# Slave.net
KiCad netlist of a schematic drawn in EAGLE
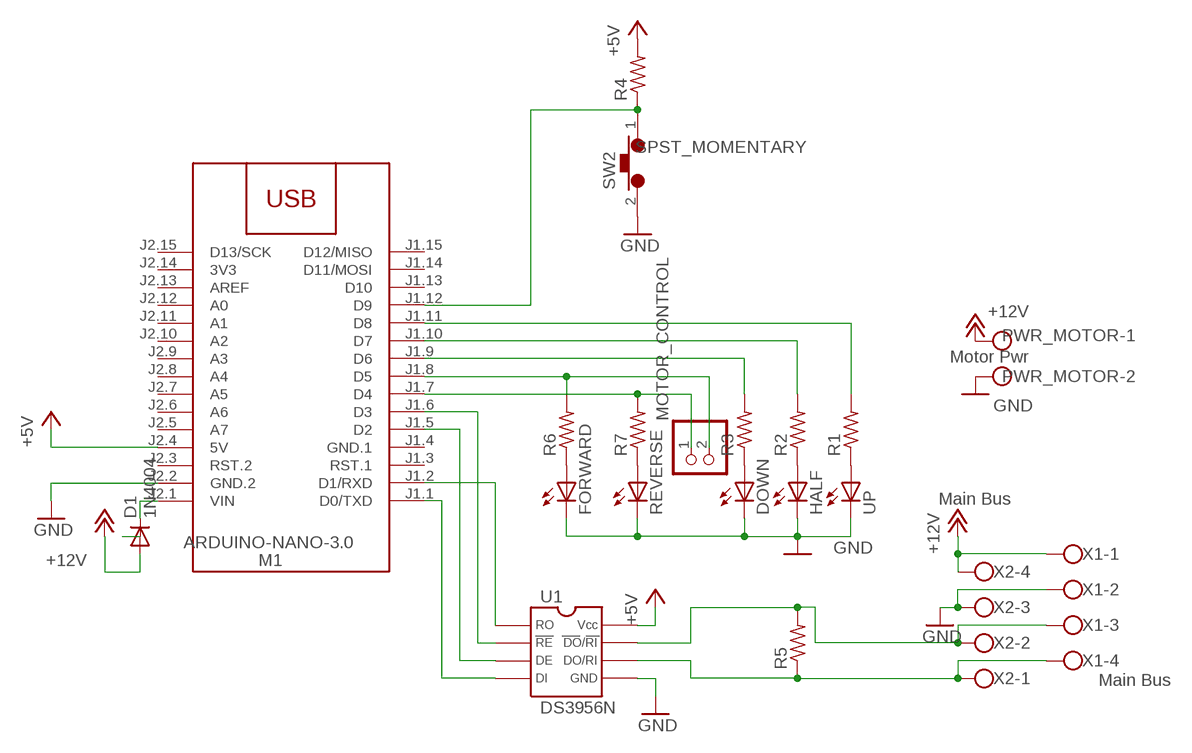
[diagram p0: schematic, sheet 1]

(export (version "E")
  (design (tool "Eeschema 10.0.6"))
  (components
    (comp (ref "D1")
      (value "1N4004")
      (footprint "eagle-import:DO41-10")
      (libsource (lib "eagle-import") (part "1N4004"))
    )
    (comp (ref "DOWN")
      (value "LED5MM")
      (footprint "eagle-import:LED5MM")
      (libsource (lib "eagle-import") (part "LED5MM"))
    )
    (comp (ref "FORWARD")
      (value "LED5MM")
      (footprint "eagle-import:LED5MM")
      (libsource (lib "eagle-import") (part "LED5MM"))
    )
    (comp (ref "HALF")
      (value "LED5MM")
      (footprint "eagle-import:LED5MM")
      (libsource (lib "eagle-import") (part "LED5MM"))
    )
    (comp (ref "M1")
      (value "ARDUINO-NANO-3.0")
      (footprint "eagle-import:ARDUINO-NANO-3.0")
      (libsource (lib "eagle-import") (part "ARDUINO-NANO-3.0"))
    )
    (comp (ref "MOTOR_CONTROL")
      (value "PINHD-1X2")
      (footprint "eagle-import:1X02")
      (libsource (lib "eagle-import") (part "PINHD-1X2"))
    )
    (comp (ref "PWR_MOTOR")
      (value "Motor Pwr")
      (footprint "eagle-import:W237-102")
      (fields (field (name "MPN") "237-102"))
      (libsource (lib "eagle-import") (part "W237-102"))
    )
    (comp (ref "R1")
      (value "FLIPFLOP-RES")
      (footprint "eagle-import:0805-THM")
      (libsource (lib "eagle-import") (part "FLIPFLOP-RES"))
    )
    (comp (ref "R2")
      (value "FLIPFLOP-RES")
      (footprint "eagle-import:0805-THM")
      (libsource (lib "eagle-import") (part "FLIPFLOP-RES"))
    )
    (comp (ref "R3")
      (value "FLIPFLOP-RES")
      (footprint "eagle-import:0805-THM")
      (libsource (lib "eagle-import") (part "FLIPFLOP-RES"))
    )
    (comp (ref "R4")
      (value "FLIPFLOP-RES")
      (footprint "eagle-import:0805-THM")
      (libsource (lib "eagle-import") (part "FLIPFLOP-RES"))
    )
    (comp (ref "R5")
      (value "FLIPFLOP-RES")
      (footprint "eagle-import:0805-THM")
      (libsource (lib "eagle-import") (part "FLIPFLOP-RES"))
    )
    (comp (ref "R6")
      (value "FLIPFLOP-RES")
      (footprint "eagle-import:0805-THM")
      (libsource (lib "eagle-import") (part "FLIPFLOP-RES"))
    )
    (comp (ref "R7")
      (value "FLIPFLOP-RES")
      (footprint "eagle-import:0805-THM")
      (libsource (lib "eagle-import") (part "FLIPFLOP-RES"))
    )
    (comp (ref "REVERSE")
      (value "LED5MM")
      (footprint "eagle-import:LED5MM")
      (libsource (lib "eagle-import") (part "LED5MM"))
    )
    (comp (ref "SW2")
      (value "SPST_MOMENTARY")
      (footprint "eagle-import:2PIN")
      (libsource (lib "eagle-import") (part "SPST_MOMENTARY"))
    )
    (comp (ref "U1")
      (value "DS3956N")
      (footprint "eagle-import:DIL08")
      (libsource (lib "eagle-import") (part "DS3956N"))
    )
    (comp (ref "UP")
      (value "LED5MM")
      (footprint "eagle-import:LED5MM")
      (libsource (lib "eagle-import") (part "LED5MM"))
    )
    (comp (ref "X1")
      (value "Main Bus")
      (footprint "eagle-import:W237-4")
      (libsource (lib "eagle-import") (part "W237-4"))
    )
    (comp (ref "X2")
      (value "Main Bus")
      (footprint "eagle-import:W237-4")
      (libsource (lib "eagle-import") (part "W237-4"))
    )
  )
  (nets
    (net (code "1") (name "+5V") (class "Default")
      (node (ref "M1") (pin "J2.4") (pinfunction "5V_J2.4") (pintype "power_in"))
      (node (ref "R4") (pin "2") (pinfunction "2_2") (pintype "passive"))
      (node (ref "U1") (pin "8") (pinfunction "VCC_8") (pintype "bidirectional"))
    )
    (net (code "2") (name "+12V") (class "Default")
      (node (ref "D1") (pin "A") (pinfunction "A_A") (pintype "passive"))
      (node (ref "PWR_MOTOR") (pin "1") (pinfunction "KL_1") (pintype "passive"))
      (node (ref "X1") (pin "1") (pinfunction "KL_1") (pintype "passive"))
      (node (ref "X2") (pin "4") (pinfunction "KL_4") (pintype "passive"))
    )
    (net (code "3") (name "/3V3") (class "Default")
      (node (ref "M1") (pin "J2.14") (pinfunction "3V3_J2.14") (pintype "power_in"))
    )
    (net (code "4") (name "/GND.1") (class "Default")
      (node (ref "M1") (pin "J1.4") (pinfunction "GND.1_J1.4") (pintype "power_in"))
    )
    (net (code "5") (name "GND") (class "Default")
      (node (ref "DOWN") (pin "K") (pinfunction "C_K") (pintype "passive"))
      (node (ref "FORWARD") (pin "K") (pinfunction "C_K") (pintype "passive"))
      (node (ref "HALF") (pin "K") (pinfunction "C_K") (pintype "passive"))
      (node (ref "M1") (pin "J2.2") (pinfunction "GND.2_J2.2") (pintype "power_in"))
      (node (ref "PWR_MOTOR") (pin "2") (pinfunction "KL_2") (pintype "passive"))
      (node (ref "REVERSE") (pin "K") (pinfunction "C_K") (pintype "passive"))
      (node (ref "SW2") (pin "2") (pinfunction "P$2_2") (pintype "bidirectional"))
      (node (ref "U1") (pin "5") (pinfunction "GND_5") (pintype "bidirectional"))
      (node (ref "UP") (pin "K") (pinfunction "C_K") (pintype "passive"))
      (node (ref "X1") (pin "2") (pinfunction "KL_2") (pintype "passive"))
      (node (ref "X2") (pin "3") (pinfunction "KL_3") (pintype "passive"))
    )
    (net (code "6") (name "Net-(DOWN-PadA)") (class "Default")
      (node (ref "DOWN") (pin "A") (pinfunction "A_A") (pintype "passive"))
      (node (ref "R3") (pin "1") (pinfunction "1_1") (pintype "passive"))
    )
    (net (code "7") (name "Net-(FORWARD-PadA)") (class "Default")
      (node (ref "FORWARD") (pin "A") (pinfunction "A_A") (pintype "passive"))
      (node (ref "R6") (pin "1") (pinfunction "1_1") (pintype "passive"))
    )
    (net (code "8") (name "Net-(HALF-PadA)") (class "Default")
      (node (ref "HALF") (pin "A") (pinfunction "A_A") (pintype "passive"))
      (node (ref "R2") (pin "1") (pinfunction "1_1") (pintype "passive"))
    )
    (net (code "9") (name "Net-(M1-D0{slash}TXD)") (class "Default")
      (node (ref "M1") (pin "J1.1") (pinfunction "D0/TXD_J1.1") (pintype "bidirectional"))
      (node (ref "U1") (pin "4") (pinfunction "DI_4") (pintype "bidirectional"))
    )
    (net (code "10") (name "Net-(M1-D1{slash}RXD)") (class "Default")
      (node (ref "M1") (pin "J1.2") (pinfunction "D1/RXD_J1.2") (pintype "bidirectional"))
      (node (ref "U1") (pin "1") (pinfunction "RO_1") (pintype "bidirectional"))
    )
    (net (code "11") (name "Net-(M1-D2)") (class "Default")
      (node (ref "M1") (pin "J1.5") (pinfunction "D2_J1.5") (pintype "bidirectional"))
      (node (ref "U1") (pin "3") (pinfunction "DE_3") (pintype "bidirectional"))
    )
    (net (code "12") (name "Net-(M1-D3)") (class "Default")
      (node (ref "M1") (pin "J1.6") (pinfunction "D3_J1.6") (pintype "bidirectional"))
      (node (ref "U1") (pin "2") (pinfunction "_RE__2") (pintype "bidirectional"))
    )
    (net (code "13") (name "Net-(M1-D4)") (class "Default")
      (node (ref "M1") (pin "J1.7") (pinfunction "D4_J1.7") (pintype "bidirectional"))
      (node (ref "MOTOR_CONTROL") (pin "1") (pinfunction "1_1") (pintype "passive"))
      (node (ref "R7") (pin "2") (pinfunction "2_2") (pintype "passive"))
    )
    (net (code "14") (name "Net-(M1-D5)") (class "Default")
      (node (ref "M1") (pin "J1.8") (pinfunction "D5_J1.8") (pintype "bidirectional"))
      (node (ref "MOTOR_CONTROL") (pin "2") (pinfunction "2_2") (pintype "passive"))
      (node (ref "R6") (pin "2") (pinfunction "2_2") (pintype "passive"))
    )
    (net (code "15") (name "Net-(M1-D6)") (class "Default")
      (node (ref "M1") (pin "J1.9") (pinfunction "D6_J1.9") (pintype "bidirectional"))
      (node (ref "R3") (pin "2") (pinfunction "2_2") (pintype "passive"))
    )
    (net (code "16") (name "Net-(M1-D7)") (class "Default")
      (node (ref "M1") (pin "J1.10") (pinfunction "D7_J1.10") (pintype "bidirectional"))
      (node (ref "R2") (pin "2") (pinfunction "2_2") (pintype "passive"))
    )
    (net (code "17") (name "Net-(M1-D8)") (class "Default")
      (node (ref "M1") (pin "J1.11") (pinfunction "D8_J1.11") (pintype "bidirectional"))
      (node (ref "R1") (pin "2") (pinfunction "2_2") (pintype "passive"))
    )
    (net (code "18") (name "Net-(M1-D9)") (class "Default")
      (node (ref "M1") (pin "J1.12") (pinfunction "D9_J1.12") (pintype "bidirectional"))
      (node (ref "R4") (pin "1") (pinfunction "1_1") (pintype "passive"))
      (node (ref "SW2") (pin "1") (pinfunction "P$1_1") (pintype "bidirectional"))
    )
    (net (code "19") (name "Net-(M1-VIN)") (class "Default")
      (node (ref "D1") (pin "C") (pinfunction "C_C") (pintype "passive"))
      (node (ref "M1") (pin "J2.1") (pinfunction "VIN_J2.1") (pintype "power_in"))
    )
    (net (code "20") (name "Net-(R1-Pad1)") (class "Default")
      (node (ref "R1") (pin "1") (pinfunction "1_1") (pintype "passive"))
      (node (ref "UP") (pin "A") (pinfunction "A_A") (pintype "passive"))
    )
    (net (code "21") (name "Net-(R7-Pad1)") (class "Default")
      (node (ref "R7") (pin "1") (pinfunction "1_1") (pintype "passive"))
      (node (ref "REVERSE") (pin "A") (pinfunction "A_A") (pintype "passive"))
    )
    (net (code "22") (name "Net-(U1-DO{slash}RI)") (class "Default")
      (node (ref "R5") (pin "1") (pinfunction "1_1") (pintype "passive"))
      (node (ref "U1") (pin "6") (pinfunction "DO/RI_6") (pintype "bidirectional"))
      (node (ref "X1") (pin "4") (pinfunction "KL_4") (pintype "passive"))
      (node (ref "X2") (pin "1") (pinfunction "KL_1") (pintype "passive"))
    )
    (net (code "23") (name "Net-(U1-_DO{slash}RI_)") (class "Default")
      (node (ref "R5") (pin "2") (pinfunction "2_2") (pintype "passive"))
      (node (ref "U1") (pin "7") (pinfunction "_DO/RI__7") (pintype "bidirectional"))
      (node (ref "X1") (pin "3") (pinfunction "KL_3") (pintype "passive"))
      (node (ref "X2") (pin "2") (pinfunction "KL_2") (pintype "passive"))
    )
    (net (code "24") (name "unconnected-(M1-A0-PadJ2.12)") (class "Default")
      (node (ref "M1") (pin "J2.12") (pinfunction "A0_J2.12") (pintype "bidirectional"))
    )
    (net (code "25") (name "unconnected-(M1-A1-PadJ2.11)") (class "Default")
      (node (ref "M1") (pin "J2.11") (pinfunction "A1_J2.11") (pintype "bidirectional"))
    )
    (net (code "26") (name "unconnected-(M1-A2-PadJ2.10)") (class "Default")
      (node (ref "M1") (pin "J2.10") (pinfunction "A2_J2.10") (pintype "bidirectional"))
    )
    (net (code "27") (name "unconnected-(M1-A3-PadJ2.9)") (class "Default")
      (node (ref "M1") (pin "J2.9") (pinfunction "A3_J2.9") (pintype "bidirectional"))
    )
    (net (code "28") (name "unconnected-(M1-A4-PadJ2.8)") (class "Default")
      (node (ref "M1") (pin "J2.8") (pinfunction "A4_J2.8") (pintype "bidirectional"))
    )
    (net (code "29") (name "unconnected-(M1-A5-PadJ2.7)") (class "Default")
      (node (ref "M1") (pin "J2.7") (pinfunction "A5_J2.7") (pintype "bidirectional"))
    )
    (net (code "30") (name "unconnected-(M1-A6-PadJ2.6)") (class "Default")
      (node (ref "M1") (pin "J2.6") (pinfunction "A6_J2.6") (pintype "bidirectional"))
    )
    (net (code "31") (name "unconnected-(M1-A7-PadJ2.5)") (class "Default")
      (node (ref "M1") (pin "J2.5") (pinfunction "A7_J2.5") (pintype "bidirectional"))
    )
    (net (code "32") (name "unconnected-(M1-AREF-PadJ2.13)") (class "Default")
      (node (ref "M1") (pin "J2.13") (pinfunction "AREF_J2.13") (pintype "bidirectional"))
    )
    (net (code "33") (name "unconnected-(M1-D10-PadJ1.13)") (class "Default")
      (node (ref "M1") (pin "J1.13") (pinfunction "D10_J1.13") (pintype "bidirectional"))
    )
    (net (code "34") (name "unconnected-(M1-D11{slash}MOSI-PadJ1.14)") (class "Default")
      (node (ref "M1") (pin "J1.14") (pinfunction "D11/MOSI_J1.14") (pintype "bidirectional"))
    )
    (net (code "35") (name "unconnected-(M1-D12{slash}MISO-PadJ1.15)") (class "Default")
      (node (ref "M1") (pin "J1.15") (pinfunction "D12/MISO_J1.15") (pintype "bidirectional"))
    )
    (net (code "36") (name "unconnected-(M1-D13{slash}SCK-PadJ2.15)") (class "Default")
      (node (ref "M1") (pin "J2.15") (pinfunction "D13/SCK_J2.15") (pintype "bidirectional"))
    )
    (net (code "37") (name "unconnected-(M1-RST.1-PadJ1.3)") (class "Default")
      (node (ref "M1") (pin "J1.3") (pinfunction "RST.1_J1.3") (pintype "bidirectional"))
    )
    (net (code "38") (name "unconnected-(M1-RST.2-PadJ2.3)") (class "Default")
      (node (ref "M1") (pin "J2.3") (pinfunction "RST.2_J2.3") (pintype "bidirectional"))
    )
  )
)
